# Connector-Sheet.net
KiCad netlist of a schematic drawn in Altium Designer
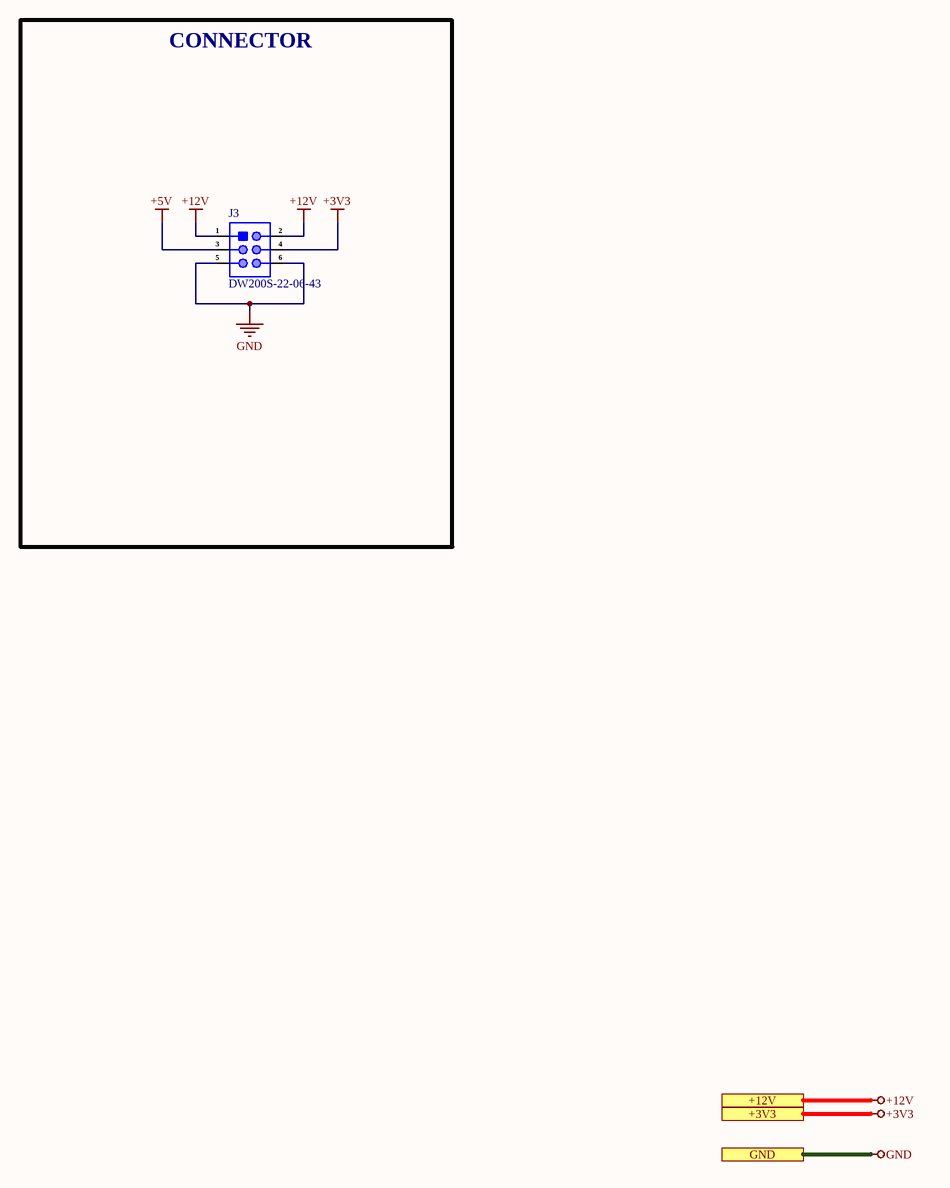
[diagram p0: Connector-Sheet.SchDoc]

(export (version "E")
  (design (tool "Eeschema 10.0.6"))
  (components
    (comp (ref "J3")
      (value "DW200S-22-06-43")
      (footprint "HDR2X3 (Female SMD)")
      (description "2mm 双排 6P Brick nogging 2x3P SMD,P=2mm Female Headers ROHS")
      (fields (field (name "MANUFACTURER") "DEALON") (field (name "LCSC PART NUMBER") "C5160809"))
      (libsource (lib "eSpark Libraries") (part "DW200S-22-06-43"))
    )
  )
  (nets
    (net (code "1") (name "+3V3") (class "Default")
      (node (ref "J3") (pin "4") (pinfunction "4_4") (pintype "passive"))
    )
    (net (code "2") (name "+5V") (class "Default")
      (node (ref "J3") (pin "3") (pinfunction "3_3") (pintype "passive"))
    )
    (net (code "3") (name "+12V") (class "Default")
      (node (ref "J3") (pin "1") (pinfunction "1_1") (pintype "passive"))
      (node (ref "J3") (pin "2") (pinfunction "2_2") (pintype "passive"))
    )
    (net (code "4") (name "GND") (class "Default")
      (node (ref "J3") (pin "5") (pinfunction "5_5") (pintype "passive"))
      (node (ref "J3") (pin "6") (pinfunction "6_6") (pintype "passive"))
    )
  )
)
